# Sch_Dr_Mag.net
KiCad netlist of a schematic drawn in Altium Designer
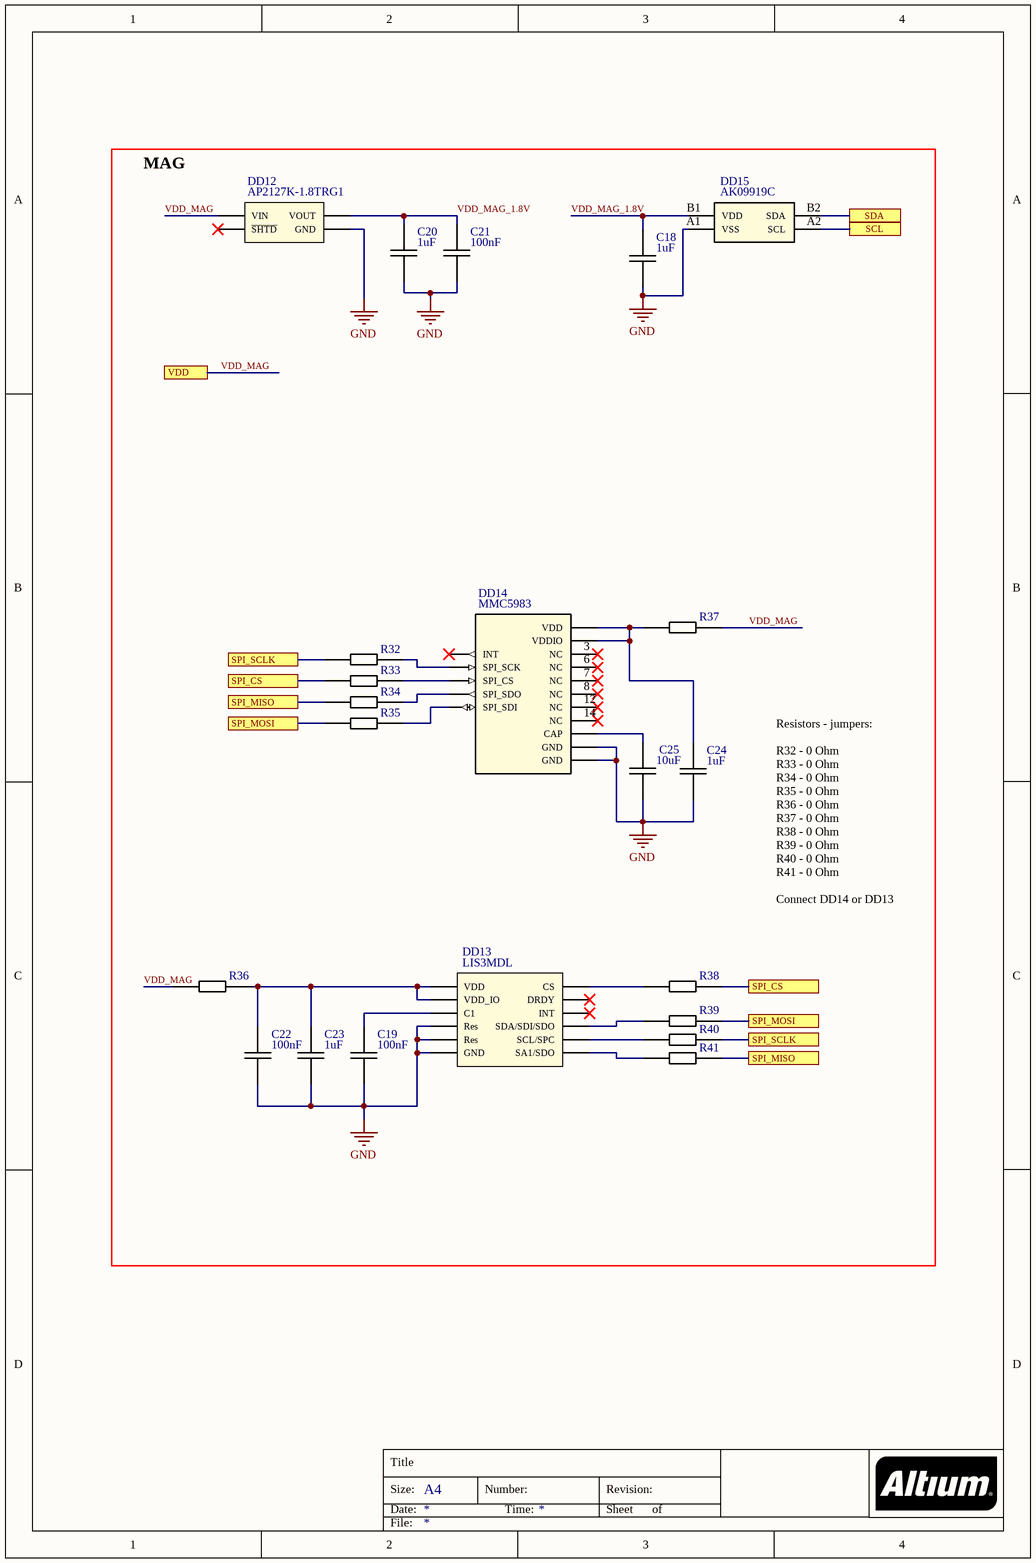
[diagram p0: Sch_Dr_Mag .SchDoc]

(export (version "E")
  (design (tool "Eeschema 10.0.6"))
  (components
    (comp (ref "C18")
      (value "1uF")
      (footprint "Cap_0603")
      (description "CC0603JRX7R7BB105")
      (libsource (lib "Dr_lib") (part "Cap_"))
    )
    (comp (ref "C19")
      (value "100nF")
      (footprint "Cap_0603")
      (description "CC0603JRX7R8BB104")
      (libsource (lib "Dr_lib") (part "Cap_"))
    )
    (comp (ref "C20")
      (value "1uF")
      (footprint "Cap_0603")
      (description "CC0603JRX7R7BB105")
      (libsource (lib "") (part "Cap__1"))
    )
    (comp (ref "C21")
      (value "100nF")
      (footprint "Cap_0603")
      (description "CC0603JRX7R8BB104")
      (libsource (lib "") (part "Cap__1"))
    )
    (comp (ref "C22")
      (value "100nF")
      (footprint "Cap_0603")
      (description "CC0603JRX7R8BB104")
      (libsource (lib "Dr_lib") (part "Cap_"))
    )
    (comp (ref "C23")
      (value "1uF")
      (footprint "Cap_0603")
      (description "CC0603JRX7R7BB105")
      (libsource (lib "Dr_lib") (part "Cap_"))
    )
    (comp (ref "C24")
      (value "1uF")
      (footprint "Cap_0603")
      (description "CC0603JRX7R7BB105")
      (libsource (lib "Dr_lib") (part "Cap_"))
    )
    (comp (ref "C25")
      (value "10uF")
      (footprint "Cap_0603")
      (description "CC0603KRX5R7BB106")
      (libsource (lib "Dr_lib") (part "Cap_"))
    )
    (comp (ref "DD12")
      (value "AP2127K-1.8TRG1")
      (footprint "SOT-23-5")
      (description "300mA High Speed, Extremely low noise CMOS LDO regulator")
      (libsource (lib "Dr_lib") (part "AP2127K-1.8TRG1"))
    )
    (comp (ref "DD13")
      (value "LIS3MDL")
      (footprint "LGA-12")
      (description "Ultra-low power, high-perfomance 3-axis magnetometer.")
      (libsource (lib "Dr_lib") (part "LIS3MDL"))
    )
    (comp (ref "DD14")
      (value "MMC5983")
      (footprint "LGA-16")
      (description "3-axis Magnetic Sensor")
      (libsource (lib "Dr_lib") (part "MMC5983"))
    )
    (comp (ref "DD15")
      (value "AK09919C")
      (footprint "AK09916")
      (description "3-axis Electronic Compass, 1.8V.")
      (libsource (lib "Dr_lib") (part "AK09919C"))
    )
    (comp (ref "R32")
      (value "0")
      (footprint "Res_0402")
      (description "RC0402FR-070RL")
      (libsource (lib "Dr_lib") (part "Res_"))
    )
    (comp (ref "R33")
      (value "0")
      (footprint "Res_0402")
      (description "RC0402FR-070RL")
      (libsource (lib "Dr_lib") (part "Res_"))
    )
    (comp (ref "R34")
      (value "0")
      (footprint "Res_0402")
      (description "RC0402FR-070RL")
      (libsource (lib "Dr_lib") (part "Res_"))
    )
    (comp (ref "R35")
      (value "0")
      (footprint "Res_0402")
      (description "RC0402FR-070RL")
      (libsource (lib "Dr_lib") (part "Res_"))
    )
    (comp (ref "R36")
      (value "0")
      (footprint "Res_0402")
      (description "RC0402FR-070RL")
      (libsource (lib "Dr_lib") (part "Res_"))
    )
    (comp (ref "R37")
      (value "0")
      (footprint "Res_0402")
      (description "RC0402FR-070RL")
      (libsource (lib "Dr_lib") (part "Res_"))
    )
    (comp (ref "R38")
      (value "0")
      (footprint "Res_0402")
      (description "RC0402FR-070RL")
      (libsource (lib "Dr_lib") (part "Res_"))
    )
    (comp (ref "R39")
      (value "0")
      (footprint "Res_0402")
      (description "RC0402FR-070RL")
      (libsource (lib "Dr_lib") (part "Res_"))
    )
    (comp (ref "R40")
      (value "0")
      (footprint "Res_0402")
      (description "RC0402FR-070RL")
      (libsource (lib "Dr_lib") (part "Res_"))
    )
    (comp (ref "R41")
      (value "0")
      (footprint "Res_0402")
      (description "RC0402FR-070RL")
      (libsource (lib "Dr_lib") (part "Res_"))
    )
  )
  (nets
    (net (code "1") (name "/SCL") (class "Default")
      (node (ref "DD15") (pin "A2") (pinfunction "SCL_A2") (pintype "passive"))
    )
    (net (code "2") (name "/SDA") (class "Default")
      (node (ref "DD15") (pin "B2") (pinfunction "SDA_B2") (pintype "passive"))
    )
    (net (code "3") (name "/SPI_CS") (class "Default")
      (node (ref "R33") (pin "1") (pinfunction "1_1") (pintype "passive"))
      (node (ref "R38") (pin "2") (pinfunction "2_2") (pintype "passive"))
    )
    (net (code "4") (name "/SPI_MISO") (class "Default")
      (node (ref "R34") (pin "1") (pinfunction "1_1") (pintype "passive"))
      (node (ref "R41") (pin "2") (pinfunction "2_2") (pintype "passive"))
    )
    (net (code "5") (name "/SPI_MOSI") (class "Default")
      (node (ref "R35") (pin "1") (pinfunction "1_1") (pintype "passive"))
      (node (ref "R39") (pin "2") (pinfunction "2_2") (pintype "passive"))
    )
    (net (code "6") (name "/SPI_SCLK") (class "Default")
      (node (ref "R32") (pin "1") (pinfunction "1_1") (pintype "passive"))
      (node (ref "R40") (pin "2") (pinfunction "2_2") (pintype "passive"))
    )
    (net (code "7") (name "/VDD_MAG") (class "Default")
      (node (ref "DD12") (pin "1") (pinfunction "VIN_1") (pintype "passive"))
      (node (ref "R36") (pin "1") (pinfunction "1_1") (pintype "passive"))
      (node (ref "R37") (pin "2") (pinfunction "2_2") (pintype "passive"))
    )
    (net (code "8") (name "/VDD_MAG_1.8V") (class "Default")
      (node (ref "C18") (pin "2") (pinfunction "2_2") (pintype "passive"))
      (node (ref "C20") (pin "2") (pinfunction "2_2") (pintype "passive"))
      (node (ref "C21") (pin "2") (pinfunction "2_2") (pintype "passive"))
      (node (ref "DD12") (pin "5") (pinfunction "VOUT_5") (pintype "passive"))
      (node (ref "DD15") (pin "B1") (pinfunction "VDD_B1") (pintype "passive"))
    )
    (net (code "9") (name "GND") (class "Default")
      (node (ref "C18") (pin "1") (pinfunction "1_1") (pintype "passive"))
      (node (ref "C19") (pin "1") (pinfunction "1_1") (pintype "passive"))
      (node (ref "C20") (pin "1") (pinfunction "1_1") (pintype "passive"))
      (node (ref "C21") (pin "1") (pinfunction "1_1") (pintype "passive"))
      (node (ref "C22") (pin "1") (pinfunction "1_1") (pintype "passive"))
      (node (ref "C23") (pin "1") (pinfunction "1_1") (pintype "passive"))
      (node (ref "C24") (pin "1") (pinfunction "1_1") (pintype "passive"))
      (node (ref "C25") (pin "1") (pinfunction "1_1") (pintype "passive"))
      (node (ref "DD12") (pin "2") (pinfunction "GND_2") (pintype "passive"))
      (node (ref "DD13") (pin "12") (pinfunction "Res_12") (pintype "passive"))
      (node (ref "DD13") (pin "2") (pinfunction "Res_2") (pintype "passive"))
      (node (ref "DD13") (pin "3") (pinfunction "GND_3") (pintype "passive"))
      (node (ref "DD14") (pin "11") (pinfunction "GND_11") (pintype "passive"))
      (node (ref "DD14") (pin "9") (pinfunction "GND_9") (pintype "passive"))
      (node (ref "DD15") (pin "A1") (pinfunction "VSS_A1") (pintype "passive"))
    )
    (net (code "10") (name "Net-(DD13-C1)") (class "Default")
      (node (ref "C19") (pin "2") (pinfunction "2_2") (pintype "passive"))
      (node (ref "DD13") (pin "4") (pinfunction "C1_4") (pintype "passive"))
    )
    (net (code "11") (name "Net-(DD13-CS)") (class "Default")
      (node (ref "DD13") (pin "10") (pinfunction "CS_10") (pintype "passive"))
      (node (ref "R38") (pin "1") (pinfunction "1_1") (pintype "passive"))
    )
    (net (code "12") (name "Net-(DD13-SA1{slash}SDO)") (class "Default")
      (node (ref "DD13") (pin "9") (pinfunction "SA1/SDO_9") (pintype "passive"))
      (node (ref "R41") (pin "1") (pinfunction "1_1") (pintype "passive"))
    )
    (net (code "13") (name "Net-(DD13-SCL{slash}SPC)") (class "Default")
      (node (ref "DD13") (pin "1") (pinfunction "SCL/SPC_1") (pintype "passive"))
      (node (ref "R40") (pin "1") (pinfunction "1_1") (pintype "passive"))
    )
    (net (code "14") (name "Net-(DD13-SDA{slash}SDI{slash}SDO)") (class "Default")
      (node (ref "DD13") (pin "11") (pinfunction "SDA/SDI/SDO_11") (pintype "passive"))
      (node (ref "R39") (pin "1") (pinfunction "1_1") (pintype "passive"))
    )
    (net (code "15") (name "Net-(DD13-VDD)") (class "Default")
      (node (ref "C22") (pin "2") (pinfunction "2_2") (pintype "passive"))
      (node (ref "C23") (pin "2") (pinfunction "2_2") (pintype "passive"))
      (node (ref "DD13") (pin "5") (pinfunction "VDD_5") (pintype "passive"))
      (node (ref "DD13") (pin "6") (pinfunction "VDD_IO_6") (pintype "passive"))
      (node (ref "R36") (pin "2") (pinfunction "2_2") (pintype "passive"))
    )
    (net (code "16") (name "Net-(DD14-CAP)") (class "Default")
      (node (ref "C25") (pin "2") (pinfunction "2_2") (pintype "passive"))
      (node (ref "DD14") (pin "10") (pinfunction "CAP_10") (pintype "passive"))
    )
    (net (code "17") (name "Net-(DD14-SPI_CS)") (class "Default")
      (node (ref "DD14") (pin "4") (pinfunction "SPI_CS_4") (pintype "input"))
      (node (ref "R33") (pin "2") (pinfunction "2_2") (pintype "passive"))
    )
    (net (code "18") (name "Net-(DD14-SPI_SCK)") (class "Default")
      (node (ref "DD14") (pin "1") (pinfunction "SPI_SCK_1") (pintype "input"))
      (node (ref "R32") (pin "2") (pinfunction "2_2") (pintype "passive"))
    )
    (net (code "19") (name "Net-(DD14-SPI_SDI)") (class "Default")
      (node (ref "DD14") (pin "16") (pinfunction "SPI_SDI_16") (pintype "bidirectional"))
      (node (ref "R35") (pin "2") (pinfunction "2_2") (pintype "passive"))
    )
    (net (code "20") (name "Net-(DD14-SPI_SDO)") (class "Default")
      (node (ref "DD14") (pin "5") (pinfunction "SPI_SDO_5") (pintype "output"))
      (node (ref "R34") (pin "2") (pinfunction "2_2") (pintype "passive"))
    )
    (net (code "21") (name "Net-(DD14-VDD)") (class "Default")
      (node (ref "C24") (pin "2") (pinfunction "2_2") (pintype "passive"))
      (node (ref "DD14") (pin "13") (pinfunction "VDDIO_13") (pintype "passive"))
      (node (ref "DD14") (pin "2") (pinfunction "VDD_2") (pintype "passive"))
      (node (ref "R37") (pin "1") (pinfunction "1_1") (pintype "passive"))
    )
    (net (code "22") (name "unconnected-(DD12-~{SHTD}-Pad3)") (class "Default")
      (node (ref "DD12") (pin "3") (pinfunction "~{SHTD}_3") (pintype "passive+no_connect"))
    )
    (net (code "23") (name "unconnected-(DD13-DRDY-Pad8)") (class "Default")
      (node (ref "DD13") (pin "8") (pinfunction "DRDY_8") (pintype "passive+no_connect"))
    )
    (net (code "24") (name "unconnected-(DD13-INT-Pad7)") (class "Default")
      (node (ref "DD13") (pin "7") (pinfunction "INT_7") (pintype "passive+no_connect"))
    )
    (net (code "25") (name "unconnected-(DD14-INT-Pad15)") (class "Default")
      (node (ref "DD14") (pin "15") (pinfunction "INT_15") (pintype "output+no_connect"))
    )
    (net (code "26") (name "unconnected-(DD14-NC-Pad3)") (class "Default")
      (node (ref "DD14") (pin "3") (pinfunction "NC_3") (pintype "passive+no_connect"))
    )
    (net (code "27") (name "unconnected-(DD14-NC-Pad6)") (class "Default")
      (node (ref "DD14") (pin "6") (pinfunction "NC_6") (pintype "passive+no_connect"))
    )
    (net (code "28") (name "unconnected-(DD14-NC-Pad7)") (class "Default")
      (node (ref "DD14") (pin "7") (pinfunction "NC_7") (pintype "passive+no_connect"))
    )
    (net (code "29") (name "unconnected-(DD14-NC-Pad8)") (class "Default")
      (node (ref "DD14") (pin "8") (pinfunction "NC_8") (pintype "passive+no_connect"))
    )
    (net (code "30") (name "unconnected-(DD14-NC-Pad12)") (class "Default")
      (node (ref "DD14") (pin "12") (pinfunction "NC_12") (pintype "passive+no_connect"))
    )
    (net (code "31") (name "unconnected-(DD14-NC-Pad14)") (class "Default")
      (node (ref "DD14") (pin "14") (pinfunction "NC_14") (pintype "passive+no_connect"))
    )
  )
)
